# Water_Schematic2_1.net
KiCad netlist of a schematic drawn in EAGLE
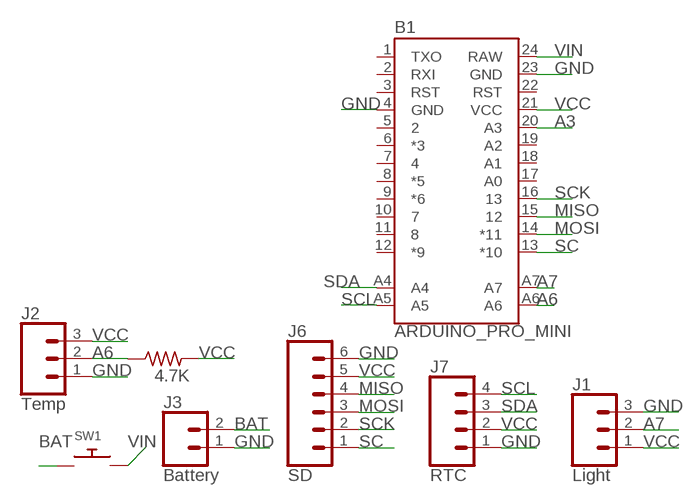
[diagram p0: schematic, sheet 1]

(export (version "E")
  (design (tool "Eeschema 10.0.6"))
  (components
    (comp (ref "B1")
      (value "ARDUINO_PRO_MINI")
      (footprint "eagle-import:ARDUINO_PRO_MINI")
      (libsource (lib "eagle-import") (part "ARDUINO_PRO_MINI"))
    )
    (comp (ref "J1")
      (value "Light")
      (footprint "eagle-import:1X03")
      (libsource (lib "eagle-import") (part "CONN_03"))
    )
    (comp (ref "J2")
      (value "Temp")
      (footprint "eagle-import:1X03")
      (libsource (lib "eagle-import") (part "CONN_03"))
    )
    (comp (ref "J3")
      (value "Battery")
      (footprint "eagle-import:MOLEX-1X2")
      (libsource (lib "eagle-import") (part "CONN_02POLAR"))
    )
    (comp (ref "J6")
      (value "SD")
      (footprint "eagle-import:1X06")
      (libsource (lib "eagle-import") (part "CONN_06SILK_FEMALE_PTH"))
    )
    (comp (ref "J7")
      (value "RTC")
      (footprint "eagle-import:MOLEX-1X4")
      (libsource (lib "eagle-import") (part "CONN_04POLAR"))
    )
    (comp (ref "R1")
      (value "4.7K")
      (footprint "eagle-import:0204_7")
      (libsource (lib "eagle-import") (part "R-US_0204/7"))
    )
    (comp (ref "SW1")
      (value "SWITCH_PUSHBUTTONEVQ-PE")
      (footprint "eagle-import:TACT_PANA-EVQ")
      (libsource (lib "eagle-import") (part "SWITCH_PUSHBUTTONEVQ-PE"))
    )
  )
  (nets
    (net (code "1") (name "/A3") (class "Default")
      (node (ref "B1") (pin "20") (pinfunction "A3_20") (pintype "bidirectional"))
    )
    (net (code "2") (name "/A6") (class "Default")
      (node (ref "B1") (pin "A6") (pinfunction "A6_A6") (pintype "bidirectional"))
      (node (ref "J2") (pin "2") (pinfunction "2_2") (pintype "passive"))
      (node (ref "R1") (pin "1") (pinfunction "1_1") (pintype "passive"))
    )
    (net (code "3") (name "/A7") (class "Default")
      (node (ref "B1") (pin "A7") (pinfunction "A7_A7") (pintype "bidirectional"))
      (node (ref "J1") (pin "2") (pinfunction "2_2") (pintype "passive"))
    )
    (net (code "4") (name "/BAT") (class "Default")
      (node (ref "J3") (pin "2") (pinfunction "2_2") (pintype "passive"))
      (node (ref "SW1") (pin "P$1") (pinfunction "P$1_P$1") (pintype "passive"))
    )
    (net (code "5") (name "/GND") (class "Default")
      (node (ref "B1") (pin "23") (pinfunction "GND_23") (pintype "power_in"))
      (node (ref "B1") (pin "4") (pinfunction "GND_4") (pintype "power_in"))
      (node (ref "J1") (pin "3") (pinfunction "3_3") (pintype "passive"))
      (node (ref "J2") (pin "1") (pinfunction "1_1") (pintype "passive"))
      (node (ref "J3") (pin "1") (pinfunction "1_1") (pintype "passive"))
      (node (ref "J6") (pin "6") (pinfunction "6_6") (pintype "passive"))
      (node (ref "J7") (pin "1") (pinfunction "1_1") (pintype "passive"))
    )
    (net (code "6") (name "/MISO") (class "Default")
      (node (ref "B1") (pin "15") (pinfunction "12_15") (pintype "bidirectional"))
      (node (ref "J6") (pin "4") (pinfunction "4_4") (pintype "passive"))
    )
    (net (code "7") (name "/MOSI") (class "Default")
      (node (ref "B1") (pin "14") (pinfunction "*11_14") (pintype "bidirectional"))
      (node (ref "J6") (pin "3") (pinfunction "3_3") (pintype "passive"))
    )
    (net (code "8") (name "/SC") (class "Default")
      (node (ref "B1") (pin "13") (pinfunction "*10_13") (pintype "bidirectional"))
      (node (ref "J6") (pin "1") (pinfunction "1_1") (pintype "passive"))
    )
    (net (code "9") (name "/SCK") (class "Default")
      (node (ref "B1") (pin "16") (pinfunction "13_16") (pintype "bidirectional"))
      (node (ref "J6") (pin "2") (pinfunction "2_2") (pintype "passive"))
    )
    (net (code "10") (name "/SCL") (class "Default")
      (node (ref "B1") (pin "A5") (pinfunction "A5_A5") (pintype "bidirectional"))
      (node (ref "J7") (pin "4") (pinfunction "4_4") (pintype "passive"))
    )
    (net (code "11") (name "/SDA") (class "Default")
      (node (ref "B1") (pin "A4") (pinfunction "A4_A4") (pintype "bidirectional"))
      (node (ref "J7") (pin "3") (pinfunction "3_3") (pintype "passive"))
    )
    (net (code "12") (name "/VCC") (class "Default")
      (node (ref "B1") (pin "21") (pinfunction "VCC_21") (pintype "power_in"))
      (node (ref "J1") (pin "1") (pinfunction "1_1") (pintype "passive"))
      (node (ref "J2") (pin "3") (pinfunction "3_3") (pintype "passive"))
      (node (ref "J6") (pin "5") (pinfunction "5_5") (pintype "passive"))
      (node (ref "J7") (pin "2") (pinfunction "2_2") (pintype "passive"))
      (node (ref "R1") (pin "2") (pinfunction "2_2") (pintype "passive"))
    )
    (net (code "13") (name "/VIN") (class "Default")
      (node (ref "B1") (pin "24") (pinfunction "RAW_24") (pintype "power_in"))
      (node (ref "SW1") (pin "P$2") (pinfunction "P$2_P$2") (pintype "passive"))
    )
    (net (code "14") (name "unconnected-(B1-*3-Pad6)") (class "Default")
      (node (ref "B1") (pin "6") (pinfunction "*3_6") (pintype "bidirectional"))
    )
    (net (code "15") (name "unconnected-(B1-*5-Pad8)") (class "Default")
      (node (ref "B1") (pin "8") (pinfunction "*5_8") (pintype "bidirectional"))
    )
    (net (code "16") (name "unconnected-(B1-*6-Pad9)") (class "Default")
      (node (ref "B1") (pin "9") (pinfunction "*6_9") (pintype "bidirectional"))
    )
    (net (code "17") (name "unconnected-(B1-*9-Pad12)") (class "Default")
      (node (ref "B1") (pin "12") (pinfunction "*9_12") (pintype "bidirectional"))
    )
    (net (code "18") (name "unconnected-(B1-2-Pad5)") (class "Default")
      (node (ref "B1") (pin "5") (pinfunction "2_5") (pintype "bidirectional"))
    )
    (net (code "19") (name "unconnected-(B1-4-Pad7)") (class "Default")
      (node (ref "B1") (pin "7") (pinfunction "4_7") (pintype "bidirectional"))
    )
    (net (code "20") (name "unconnected-(B1-7-Pad10)") (class "Default")
      (node (ref "B1") (pin "10") (pinfunction "7_10") (pintype "bidirectional"))
    )
    (net (code "21") (name "unconnected-(B1-8-Pad11)") (class "Default")
      (node (ref "B1") (pin "11") (pinfunction "8_11") (pintype "bidirectional"))
    )
    (net (code "22") (name "unconnected-(B1-A0-Pad17)") (class "Default")
      (node (ref "B1") (pin "17") (pinfunction "A0_17") (pintype "bidirectional"))
    )
    (net (code "23") (name "unconnected-(B1-A1-Pad18)") (class "Default")
      (node (ref "B1") (pin "18") (pinfunction "A1_18") (pintype "bidirectional"))
    )
    (net (code "24") (name "unconnected-(B1-A2-Pad19)") (class "Default")
      (node (ref "B1") (pin "19") (pinfunction "A2_19") (pintype "bidirectional"))
    )
    (net (code "25") (name "unconnected-(B1-RST-Pad3)") (class "Default")
      (node (ref "B1") (pin "3") (pinfunction "RST_3") (pintype "bidirectional"))
    )
    (net (code "26") (name "unconnected-(B1-RST-Pad22)") (class "Default")
      (node (ref "B1") (pin "22") (pinfunction "RST_22") (pintype "bidirectional"))
    )
    (net (code "27") (name "unconnected-(B1-RXI-Pad2)") (class "Default")
      (node (ref "B1") (pin "2") (pinfunction "RXI_2") (pintype "bidirectional"))
    )
    (net (code "28") (name "unconnected-(B1-TXO-Pad1)") (class "Default")
      (node (ref "B1") (pin "1") (pinfunction "TXO_1") (pintype "bidirectional"))
    )
  )
)
